# CrackberryPi_1_0_6_2_parts.net
KiCad netlist of a schematic drawn in EAGLE
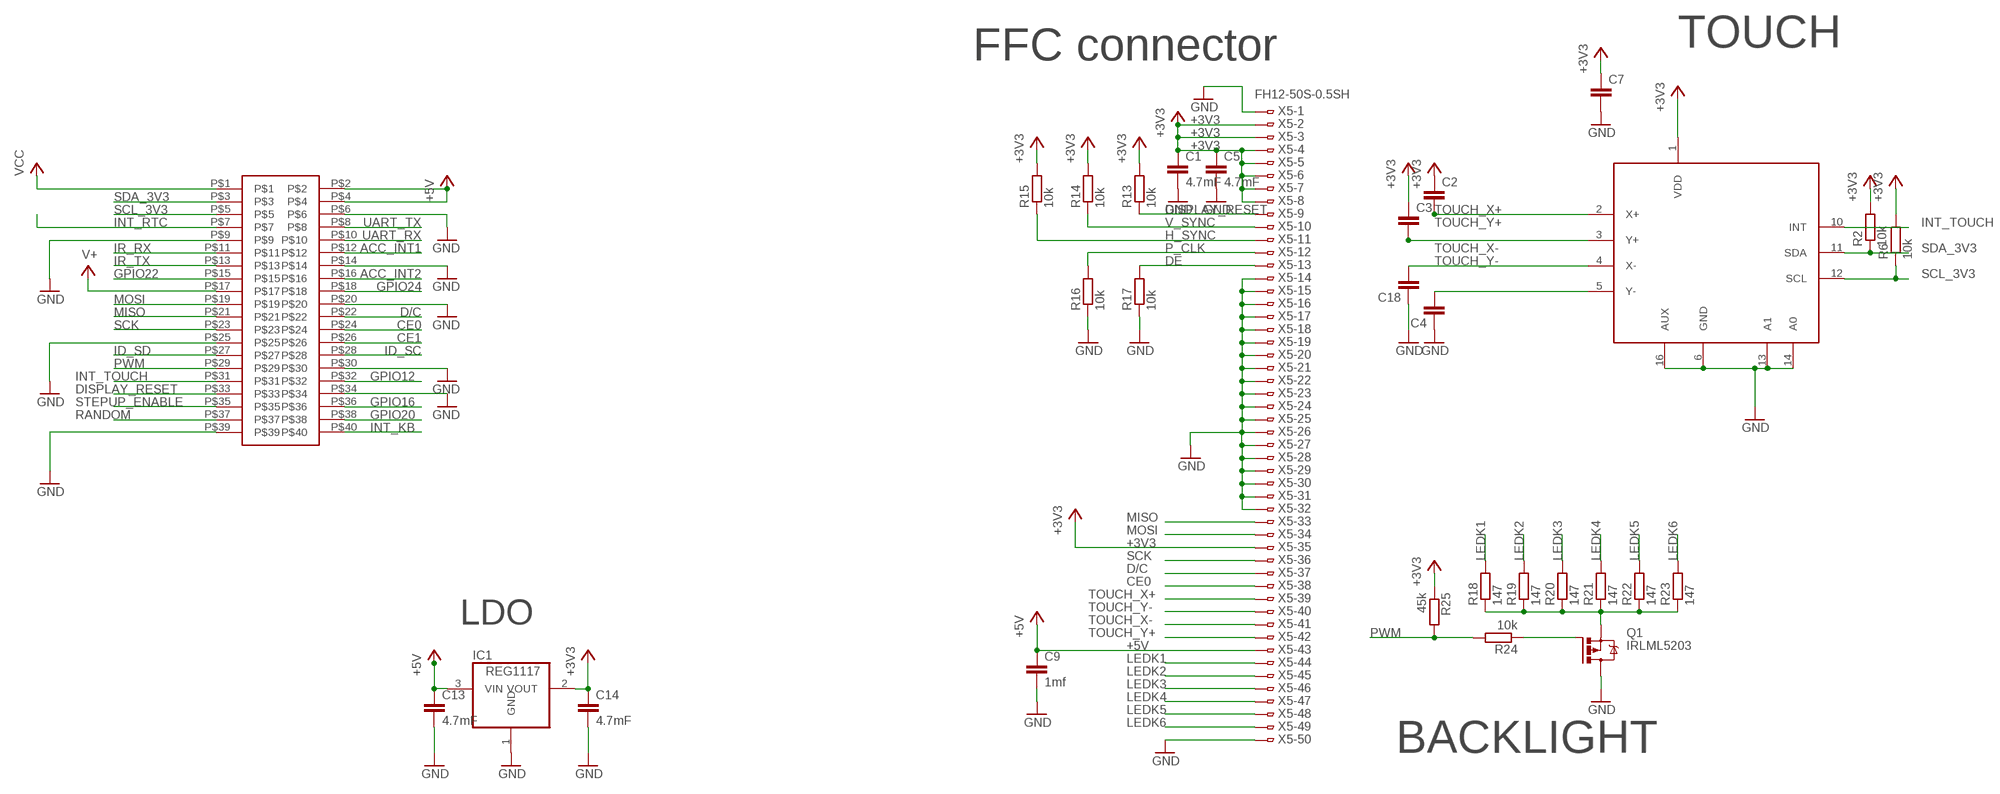
[diagram p0: schematic, sheet 1]

(export (version "E")
  (design (tool "Eeschema 10.0.6"))
  (components
    (comp (ref "C1")
      (value "4.7mF")
      (footprint "eagle-import:C0603")
      (libsource (lib "eagle-import") (part "C-EUC0603"))
    )
    (comp (ref "C2")
      (value "C-EUC0603")
      (footprint "eagle-import:C0603")
      (libsource (lib "eagle-import") (part "C-EUC0603"))
    )
    (comp (ref "C3")
      (value "C-EUC0603")
      (footprint "eagle-import:C0603")
      (libsource (lib "eagle-import") (part "C-EUC0603"))
    )
    (comp (ref "C4")
      (value "C-EUC0603")
      (footprint "eagle-import:C0603")
      (libsource (lib "eagle-import") (part "C-EUC0603"))
    )
    (comp (ref "C5")
      (value "4.7mF")
      (footprint "eagle-import:C0603")
      (libsource (lib "eagle-import") (part "C-EUC0603"))
    )
    (comp (ref "C7")
      (value "C-EUC0603")
      (footprint "eagle-import:C0603")
      (libsource (lib "eagle-import") (part "C-EUC0603"))
    )
    (comp (ref "C9")
      (value "1mf")
      (footprint "eagle-import:C0603")
      (libsource (lib "eagle-import") (part "C-EUC0603"))
    )
    (comp (ref "C13")
      (value "4.7mF")
      (footprint "eagle-import:C0603")
      (libsource (lib "eagle-import") (part "C-EUC0603"))
    )
    (comp (ref "C14")
      (value "4.7mF")
      (footprint "eagle-import:C0603")
      (libsource (lib "eagle-import") (part "C-EUC0603"))
    )
    (comp (ref "C18")
      (value "C-EUC0603")
      (footprint "eagle-import:C0603")
      (libsource (lib "eagle-import") (part "C-EUC0603"))
    )
    (comp (ref "IC1")
      (value "REG1117")
      (footprint "eagle-import:SOT223")
      (libsource (lib "eagle-import") (part "REG1117"))
    )
    (comp (ref "Q1")
      (value "IRLML5203")
      (footprint "eagle-import:MICRO3")
      (libsource (lib "eagle-import") (part "IRLML5203"))
    )
    (comp (ref "R2")
      (value "10k")
      (footprint "eagle-import:R0603")
      (libsource (lib "eagle-import") (part "R-EU_R0603"))
    )
    (comp (ref "R6")
      (value "10k")
      (footprint "eagle-import:R0603")
      (libsource (lib "eagle-import") (part "R-EU_R0603"))
    )
    (comp (ref "R13")
      (value "10k")
      (footprint "eagle-import:R0603")
      (libsource (lib "eagle-import") (part "R-EU_R0603"))
    )
    (comp (ref "R14")
      (value "10k")
      (footprint "eagle-import:R0603")
      (libsource (lib "eagle-import") (part "R-EU_R0603"))
    )
    (comp (ref "R15")
      (value "10k")
      (footprint "eagle-import:R0603")
      (libsource (lib "eagle-import") (part "R-EU_R0603"))
    )
    (comp (ref "R16")
      (value "10k")
      (footprint "eagle-import:R0603")
      (libsource (lib "eagle-import") (part "R-EU_R0603"))
    )
    (comp (ref "R17")
      (value "10k")
      (footprint "eagle-import:R0603")
      (libsource (lib "eagle-import") (part "R-EU_R0603"))
    )
    (comp (ref "R18")
      (value "147")
      (footprint "eagle-import:R0603")
      (libsource (lib "eagle-import") (part "R-EU_R0603"))
    )
    (comp (ref "R19")
      (value "147")
      (footprint "eagle-import:R0603")
      (libsource (lib "eagle-import") (part "R-EU_R0603"))
    )
    (comp (ref "R20")
      (value "147")
      (footprint "eagle-import:R0603")
      (libsource (lib "eagle-import") (part "R-EU_R0603"))
    )
    (comp (ref "R21")
      (value "147")
      (footprint "eagle-import:R0603")
      (libsource (lib "eagle-import") (part "R-EU_R0603"))
    )
    (comp (ref "R22")
      (value "147")
      (footprint "eagle-import:R0603")
      (libsource (lib "eagle-import") (part "R-EU_R0603"))
    )
    (comp (ref "R23")
      (value "147")
      (footprint "eagle-import:R0603")
      (libsource (lib "eagle-import") (part "R-EU_R0603"))
    )
    (comp (ref "R24")
      (value "10k")
      (footprint "eagle-import:R0603")
      (libsource (lib "eagle-import") (part "R-EU_R0603"))
    )
    (comp (ref "R25")
      (value "45k")
      (footprint "eagle-import:R0603")
      (libsource (lib "eagle-import") (part "R-EU_R0603"))
    )
    (comp (ref "U$6")
      (value "TSC2007")
      (footprint "eagle-import:TSSOP16")
      (libsource (lib "eagle-import") (part "TSC2007"))
    )
    (comp (ref "U$11")
      (value "HEADER")
      (footprint "eagle-import:20X2")
      (libsource (lib "eagle-import") (part "HEADER"))
    )
    (comp (ref "X5")
      (value "FH12-50S-0.5SH")
      (footprint "eagle-import:FH12-50S-0.5SH")
      (fields (field (name "MPN") "FH12-50S-0.5SH(55)"))
      (libsource (lib "eagle-import") (part "FH12-50S-0.5SH"))
    )
  )
  (nets
    (net (code "1") (name "+3V3") (class "Default")
      (node (ref "C1") (pin "1") (pinfunction "1_1") (pintype "passive"))
      (node (ref "C14") (pin "1") (pinfunction "1_1") (pintype "passive"))
      (node (ref "C2") (pin "1") (pinfunction "1_1") (pintype "passive"))
      (node (ref "C3") (pin "1") (pinfunction "1_1") (pintype "passive"))
      (node (ref "C5") (pin "1") (pinfunction "1_1") (pintype "passive"))
      (node (ref "C7") (pin "1") (pinfunction "1_1") (pintype "passive"))
      (node (ref "IC1") (pin "2") (pinfunction "VOUT_2") (pintype "output"))
      (node (ref "R13") (pin "2") (pinfunction "2_2") (pintype "passive"))
      (node (ref "R14") (pin "2") (pinfunction "2_2") (pintype "passive"))
      (node (ref "R15") (pin "2") (pinfunction "2_2") (pintype "passive"))
      (node (ref "R2") (pin "2") (pinfunction "2_2") (pintype "passive"))
      (node (ref "R25") (pin "1") (pinfunction "1_1") (pintype "passive"))
      (node (ref "R6") (pin "2") (pinfunction "2_2") (pintype "passive"))
      (node (ref "U$6") (pin "1") (pinfunction "VDD_1") (pintype "bidirectional"))
      (node (ref "X5") (pin "2") (pinfunction "1_2") (pintype "passive"))
      (node (ref "X5") (pin "3") (pinfunction "1_3") (pintype "passive"))
      (node (ref "X5") (pin "35") (pinfunction "1_35") (pintype "passive"))
      (node (ref "X5") (pin "4") (pinfunction "1_4") (pintype "passive"))
      (node (ref "X5") (pin "5") (pinfunction "1_5") (pintype "passive"))
      (node (ref "X5") (pin "6") (pinfunction "1_6") (pintype "passive"))
      (node (ref "X5") (pin "7") (pinfunction "1_7") (pintype "passive"))
      (node (ref "X5") (pin "8") (pinfunction "1_8") (pintype "passive"))
    )
    (net (code "2") (name "+5V") (class "Default")
      (node (ref "C13") (pin "1") (pinfunction "1_1") (pintype "passive"))
      (node (ref "C9") (pin "1") (pinfunction "1_1") (pintype "passive"))
      (node (ref "IC1") (pin "3") (pinfunction "VIN_3") (pintype "input"))
      (node (ref "U$11") (pin "P$2") (pinfunction "P$2_P$2") (pintype "bidirectional"))
      (node (ref "U$11") (pin "P$4") (pinfunction "P$4_P$4") (pintype "bidirectional"))
      (node (ref "X5") (pin "43") (pinfunction "1_43") (pintype "passive"))
    )
    (net (code "3") (name "/ACC_INT1") (class "Default")
      (node (ref "U$11") (pin "P$12") (pinfunction "P$12_P$12") (pintype "bidirectional"))
    )
    (net (code "4") (name "/ACC_INT2") (class "Default")
      (node (ref "U$11") (pin "P$16") (pinfunction "P$16_P$16") (pintype "bidirectional"))
    )
    (net (code "5") (name "/CE0") (class "Default")
      (node (ref "U$11") (pin "P$24") (pinfunction "P$24_P$24") (pintype "bidirectional"))
      (node (ref "X5") (pin "38") (pinfunction "1_38") (pintype "passive"))
    )
    (net (code "6") (name "/CE1") (class "Default")
      (node (ref "U$11") (pin "P$26") (pinfunction "P$26_P$26") (pintype "bidirectional"))
    )
    (net (code "7") (name "/DE") (class "Default")
      (node (ref "R17") (pin "2") (pinfunction "2_2") (pintype "passive"))
      (node (ref "X5") (pin "13") (pinfunction "1_13") (pintype "passive"))
    )
    (net (code "8") (name "/DISPLAY_RESET") (class "Default")
      (node (ref "R13") (pin "1") (pinfunction "1_1") (pintype "passive"))
      (node (ref "U$11") (pin "P$33") (pinfunction "P$33_P$33") (pintype "bidirectional"))
      (node (ref "X5") (pin "9") (pinfunction "1_9") (pintype "passive"))
    )
    (net (code "9") (name "/D{slash}C") (class "Default")
      (node (ref "U$11") (pin "P$22") (pinfunction "P$22_P$22") (pintype "bidirectional"))
      (node (ref "X5") (pin "37") (pinfunction "1_37") (pintype "passive"))
    )
    (net (code "10") (name "/GPIO12") (class "Default")
      (node (ref "U$11") (pin "P$32") (pinfunction "P$32_P$32") (pintype "bidirectional"))
    )
    (net (code "11") (name "/GPIO16") (class "Default")
      (node (ref "U$11") (pin "P$36") (pinfunction "P$36_P$36") (pintype "bidirectional"))
    )
    (net (code "12") (name "/GPIO20") (class "Default")
      (node (ref "U$11") (pin "P$38") (pinfunction "P$38_P$38") (pintype "bidirectional"))
    )
    (net (code "13") (name "/GPIO22") (class "Default")
      (node (ref "U$11") (pin "P$15") (pinfunction "P$15_P$15") (pintype "bidirectional"))
    )
    (net (code "14") (name "/GPIO24") (class "Default")
      (node (ref "U$11") (pin "P$18") (pinfunction "P$18_P$18") (pintype "bidirectional"))
    )
    (net (code "15") (name "/H_SYNC") (class "Default")
      (node (ref "R15") (pin "1") (pinfunction "1_1") (pintype "passive"))
      (node (ref "X5") (pin "11") (pinfunction "1_11") (pintype "passive"))
    )
    (net (code "16") (name "/ID_SC") (class "Default")
      (node (ref "U$11") (pin "P$28") (pinfunction "P$28_P$28") (pintype "bidirectional"))
    )
    (net (code "17") (name "/ID_SD") (class "Default")
      (node (ref "U$11") (pin "P$27") (pinfunction "P$27_P$27") (pintype "bidirectional"))
    )
    (net (code "18") (name "/INT_KB") (class "Default")
      (node (ref "U$11") (pin "P$40") (pinfunction "P$40_P$40") (pintype "bidirectional"))
    )
    (net (code "19") (name "/INT_RTC") (class "Default")
      (node (ref "U$11") (pin "P$7") (pinfunction "P$7_P$7") (pintype "bidirectional"))
    )
    (net (code "20") (name "/INT_TOUCH") (class "Default")
      (node (ref "U$11") (pin "P$31") (pinfunction "P$31_P$31") (pintype "bidirectional"))
      (node (ref "U$6") (pin "10") (pinfunction "INT_10") (pintype "bidirectional"))
    )
    (net (code "21") (name "/IR_RX") (class "Default")
      (node (ref "U$11") (pin "P$11") (pinfunction "P$11_P$11") (pintype "bidirectional"))
    )
    (net (code "22") (name "/IR_TX") (class "Default")
      (node (ref "U$11") (pin "P$13") (pinfunction "P$13_P$13") (pintype "bidirectional"))
    )
    (net (code "23") (name "/LEDK1") (class "Default")
      (node (ref "R18") (pin "2") (pinfunction "2_2") (pintype "passive"))
      (node (ref "X5") (pin "44") (pinfunction "1_44") (pintype "passive"))
    )
    (net (code "24") (name "/LEDK2") (class "Default")
      (node (ref "R19") (pin "2") (pinfunction "2_2") (pintype "passive"))
      (node (ref "X5") (pin "45") (pinfunction "1_45") (pintype "passive"))
    )
    (net (code "25") (name "/LEDK3") (class "Default")
      (node (ref "R20") (pin "2") (pinfunction "2_2") (pintype "passive"))
      (node (ref "X5") (pin "46") (pinfunction "1_46") (pintype "passive"))
    )
    (net (code "26") (name "/LEDK4") (class "Default")
      (node (ref "R21") (pin "2") (pinfunction "2_2") (pintype "passive"))
      (node (ref "X5") (pin "47") (pinfunction "1_47") (pintype "passive"))
    )
    (net (code "27") (name "/LEDK5") (class "Default")
      (node (ref "R22") (pin "2") (pinfunction "2_2") (pintype "passive"))
      (node (ref "X5") (pin "48") (pinfunction "1_48") (pintype "passive"))
    )
    (net (code "28") (name "/LEDK6") (class "Default")
      (node (ref "R23") (pin "2") (pinfunction "2_2") (pintype "passive"))
      (node (ref "X5") (pin "49") (pinfunction "1_49") (pintype "passive"))
    )
    (net (code "29") (name "/MISO") (class "Default")
      (node (ref "U$11") (pin "P$21") (pinfunction "P$21_P$21") (pintype "bidirectional"))
      (node (ref "X5") (pin "33") (pinfunction "1_33") (pintype "passive"))
    )
    (net (code "30") (name "/MOSI") (class "Default")
      (node (ref "U$11") (pin "P$19") (pinfunction "P$19_P$19") (pintype "bidirectional"))
      (node (ref "X5") (pin "34") (pinfunction "1_34") (pintype "passive"))
    )
    (net (code "31") (name "/PWM") (class "Default")
      (node (ref "R24") (pin "2") (pinfunction "2_2") (pintype "passive"))
      (node (ref "R25") (pin "2") (pinfunction "2_2") (pintype "passive"))
      (node (ref "U$11") (pin "P$29") (pinfunction "P$29_P$29") (pintype "bidirectional"))
    )
    (net (code "32") (name "/P_CLK") (class "Default")
      (node (ref "R16") (pin "2") (pinfunction "2_2") (pintype "passive"))
      (node (ref "X5") (pin "12") (pinfunction "1_12") (pintype "passive"))
    )
    (net (code "33") (name "/RANDOM") (class "Default")
      (node (ref "U$11") (pin "P$37") (pinfunction "P$37_P$37") (pintype "bidirectional"))
    )
    (net (code "34") (name "/SCK") (class "Default")
      (node (ref "U$11") (pin "P$23") (pinfunction "P$23_P$23") (pintype "bidirectional"))
      (node (ref "X5") (pin "36") (pinfunction "1_36") (pintype "passive"))
    )
    (net (code "35") (name "/SCL_3V3") (class "Default")
      (node (ref "R6") (pin "1") (pinfunction "1_1") (pintype "passive"))
      (node (ref "U$11") (pin "P$5") (pinfunction "P$5_P$5") (pintype "bidirectional"))
      (node (ref "U$6") (pin "12") (pinfunction "SCL_12") (pintype "bidirectional"))
    )
    (net (code "36") (name "/SDA_3V3") (class "Default")
      (node (ref "R2") (pin "1") (pinfunction "1_1") (pintype "passive"))
      (node (ref "U$11") (pin "P$3") (pinfunction "P$3_P$3") (pintype "bidirectional"))
      (node (ref "U$6") (pin "11") (pinfunction "SDA_11") (pintype "bidirectional"))
    )
    (net (code "37") (name "/STEPUP_ENABLE") (class "Default")
      (node (ref "U$11") (pin "P$35") (pinfunction "P$35_P$35") (pintype "bidirectional"))
    )
    (net (code "38") (name "/TOUCH_X+") (class "Default")
      (node (ref "C2") (pin "2") (pinfunction "2_2") (pintype "passive"))
      (node (ref "U$6") (pin "2") (pinfunction "X+_2") (pintype "bidirectional"))
      (node (ref "X5") (pin "39") (pinfunction "1_39") (pintype "passive"))
    )
    (net (code "39") (name "/TOUCH_X-") (class "Default")
      (node (ref "C18") (pin "2") (pinfunction "2_2") (pintype "passive"))
      (node (ref "U$6") (pin "4") (pinfunction "X-_4") (pintype "bidirectional"))
      (node (ref "X5") (pin "41") (pinfunction "1_41") (pintype "passive"))
    )
    (net (code "40") (name "/TOUCH_Y+") (class "Default")
      (node (ref "C3") (pin "2") (pinfunction "2_2") (pintype "passive"))
      (node (ref "U$6") (pin "3") (pinfunction "Y+_3") (pintype "bidirectional"))
      (node (ref "X5") (pin "42") (pinfunction "1_42") (pintype "passive"))
    )
    (net (code "41") (name "/TOUCH_Y-") (class "Default")
      (node (ref "C4") (pin "2") (pinfunction "2_2") (pintype "passive"))
      (node (ref "U$6") (pin "5") (pinfunction "Y-_5") (pintype "bidirectional"))
      (node (ref "X5") (pin "40") (pinfunction "1_40") (pintype "passive"))
    )
    (net (code "42") (name "/UART_RX") (class "Default")
      (node (ref "U$11") (pin "P$10") (pinfunction "P$10_P$10") (pintype "bidirectional"))
    )
    (net (code "43") (name "/UART_TX") (class "Default")
      (node (ref "U$11") (pin "P$8") (pinfunction "P$8_P$8") (pintype "bidirectional"))
    )
    (net (code "44") (name "/V_SYNC") (class "Default")
      (node (ref "R14") (pin "1") (pinfunction "1_1") (pintype "passive"))
      (node (ref "X5") (pin "10") (pinfunction "1_10") (pintype "passive"))
    )
    (net (code "45") (name "GND") (class "Default")
      (node (ref "C1") (pin "2") (pinfunction "2_2") (pintype "passive"))
      (node (ref "C13") (pin "2") (pinfunction "2_2") (pintype "passive"))
      (node (ref "C14") (pin "2") (pinfunction "2_2") (pintype "passive"))
      (node (ref "C18") (pin "1") (pinfunction "1_1") (pintype "passive"))
      (node (ref "C4") (pin "1") (pinfunction "1_1") (pintype "passive"))
      (node (ref "C5") (pin "2") (pinfunction "2_2") (pintype "passive"))
      (node (ref "C7") (pin "2") (pinfunction "2_2") (pintype "passive"))
      (node (ref "C9") (pin "2") (pinfunction "2_2") (pintype "passive"))
      (node (ref "IC1") (pin "1") (pinfunction "GND_1") (pintype "power_in"))
      (node (ref "Q1") (pin "3") (pinfunction "D_3") (pintype "passive"))
      (node (ref "R16") (pin "1") (pinfunction "1_1") (pintype "passive"))
      (node (ref "R17") (pin "1") (pinfunction "1_1") (pintype "passive"))
      (node (ref "U$11") (pin "P$14") (pinfunction "P$14_P$14") (pintype "bidirectional"))
      (node (ref "U$11") (pin "P$20") (pinfunction "P$20_P$20") (pintype "bidirectional"))
      (node (ref "U$11") (pin "P$25") (pinfunction "P$25_P$25") (pintype "bidirectional"))
      (node (ref "U$11") (pin "P$30") (pinfunction "P$30_P$30") (pintype "bidirectional"))
      (node (ref "U$11") (pin "P$34") (pinfunction "P$34_P$34") (pintype "bidirectional"))
      (node (ref "U$11") (pin "P$39") (pinfunction "P$39_P$39") (pintype "bidirectional"))
      (node (ref "U$11") (pin "P$6") (pinfunction "P$6_P$6") (pintype "bidirectional"))
      (node (ref "U$11") (pin "P$9") (pinfunction "P$9_P$9") (pintype "bidirectional"))
      (node (ref "U$6") (pin "13") (pinfunction "A1_13") (pintype "bidirectional"))
      (node (ref "U$6") (pin "14") (pinfunction "A0_14") (pintype "bidirectional"))
      (node (ref "U$6") (pin "16") (pinfunction "AUX_16") (pintype "bidirectional"))
      (node (ref "U$6") (pin "6") (pinfunction "GND_6") (pintype "bidirectional"))
      (node (ref "X5") (pin "1") (pinfunction "1_1") (pintype "passive"))
      (node (ref "X5") (pin "14") (pinfunction "1_14") (pintype "passive"))
      (node (ref "X5") (pin "15") (pinfunction "1_15") (pintype "passive"))
      (node (ref "X5") (pin "16") (pinfunction "1_16") (pintype "passive"))
      (node (ref "X5") (pin "17") (pinfunction "1_17") (pintype "passive"))
      (node (ref "X5") (pin "18") (pinfunction "1_18") (pintype "passive"))
      (node (ref "X5") (pin "19") (pinfunction "1_19") (pintype "passive"))
      (node (ref "X5") (pin "20") (pinfunction "1_20") (pintype "passive"))
      (node (ref "X5") (pin "21") (pinfunction "1_21") (pintype "passive"))
      (node (ref "X5") (pin "22") (pinfunction "1_22") (pintype "passive"))
      (node (ref "X5") (pin "23") (pinfunction "1_23") (pintype "passive"))
      (node (ref "X5") (pin "24") (pinfunction "1_24") (pintype "passive"))
      (node (ref "X5") (pin "25") (pinfunction "1_25") (pintype "passive"))
      (node (ref "X5") (pin "26") (pinfunction "1_26") (pintype "passive"))
      (node (ref "X5") (pin "27") (pinfunction "1_27") (pintype "passive"))
      (node (ref "X5") (pin "28") (pinfunction "1_28") (pintype "passive"))
      (node (ref "X5") (pin "29") (pinfunction "1_29") (pintype "passive"))
      (node (ref "X5") (pin "30") (pinfunction "1_30") (pintype "passive"))
      (node (ref "X5") (pin "31") (pinfunction "1_31") (pintype "passive"))
      (node (ref "X5") (pin "32") (pinfunction "1_32") (pintype "passive"))
      (node (ref "X5") (pin "50") (pinfunction "1_50") (pintype "passive"))
    )
    (net (code "46") (name "Net-(Q1-G)") (class "Default")
      (node (ref "Q1") (pin "1") (pinfunction "G_1") (pintype "passive"))
      (node (ref "R24") (pin "1") (pinfunction "1_1") (pintype "passive"))
    )
    (net (code "47") (name "Net-(Q1-S)") (class "Default")
      (node (ref "Q1") (pin "2") (pinfunction "S_2") (pintype "passive"))
      (node (ref "R18") (pin "1") (pinfunction "1_1") (pintype "passive"))
      (node (ref "R19") (pin "1") (pinfunction "1_1") (pintype "passive"))
      (node (ref "R20") (pin "1") (pinfunction "1_1") (pintype "passive"))
      (node (ref "R21") (pin "1") (pinfunction "1_1") (pintype "passive"))
      (node (ref "R22") (pin "1") (pinfunction "1_1") (pintype "passive"))
      (node (ref "R23") (pin "1") (pinfunction "1_1") (pintype "passive"))
    )
    (net (code "48") (name "V+") (class "Default")
      (node (ref "U$11") (pin "P$17") (pinfunction "P$17_P$17") (pintype "bidirectional"))
    )
    (net (code "49") (name "VCC") (class "Default")
      (node (ref "U$11") (pin "P$1") (pinfunction "P$1_P$1") (pintype "bidirectional"))
    )
  )
)
